# MaximConnections.net
KiCad netlist of a schematic drawn in Altium Designer
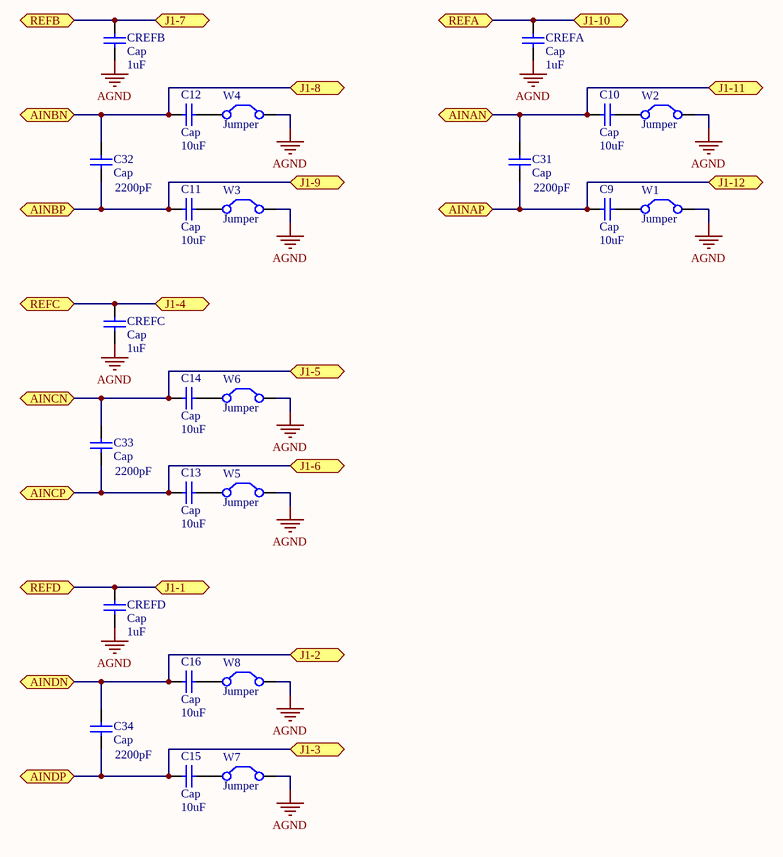
[diagram p0: MaximConnections.SchDoc]

(export (version "E")
  (design (tool "Eeschema 10.0.6"))
  (components
    (comp (ref "C9")
      (value "Cap")
      (footprint "RAD-0.3")
      (description "Capacitor")
      (fields (field (name "ALTIUM_VALUE") "10uF") (field (name "PUBLISHER") "Altium Limited"))
      (libsource (lib "Miscellaneous Devices") (part "Cap"))
    )
    (comp (ref "C10")
      (value "Cap")
      (footprint "RAD-0.3")
      (description "Capacitor")
      (fields (field (name "ALTIUM_VALUE") "10uF") (field (name "PUBLISHER") "Altium Limited"))
      (libsource (lib "Miscellaneous Devices") (part "Cap"))
    )
    (comp (ref "C11")
      (value "Cap")
      (footprint "RAD-0.3")
      (description "Capacitor")
      (fields (field (name "ALTIUM_VALUE") "10uF") (field (name "PUBLISHER") "Altium Limited"))
      (libsource (lib "Miscellaneous Devices") (part "Cap"))
    )
    (comp (ref "C12")
      (value "Cap")
      (footprint "RAD-0.3")
      (description "Capacitor")
      (fields (field (name "ALTIUM_VALUE") "10uF") (field (name "PUBLISHER") "Altium Limited"))
      (libsource (lib "Miscellaneous Devices") (part "Cap"))
    )
    (comp (ref "C13")
      (value "Cap")
      (footprint "RAD-0.3")
      (description "Capacitor")
      (fields (field (name "ALTIUM_VALUE") "10uF") (field (name "PUBLISHER") "Altium Limited"))
      (libsource (lib "Miscellaneous Devices") (part "Cap"))
    )
    (comp (ref "C14")
      (value "Cap")
      (footprint "RAD-0.3")
      (description "Capacitor")
      (fields (field (name "ALTIUM_VALUE") "10uF") (field (name "PUBLISHER") "Altium Limited"))
      (libsource (lib "Miscellaneous Devices") (part "Cap"))
    )
    (comp (ref "C15")
      (value "Cap")
      (footprint "RAD-0.3")
      (description "Capacitor")
      (fields (field (name "ALTIUM_VALUE") "10uF") (field (name "PUBLISHER") "Altium Limited"))
      (libsource (lib "Miscellaneous Devices") (part "Cap"))
    )
    (comp (ref "C16")
      (value "Cap")
      (footprint "RAD-0.3")
      (description "Capacitor")
      (fields (field (name "ALTIUM_VALUE") "10uF") (field (name "PUBLISHER") "Altium Limited"))
      (libsource (lib "Miscellaneous Devices") (part "Cap"))
    )
    (comp (ref "C31")
      (value "Cap")
      (footprint "RAD-0.3")
      (description "Capacitor")
      (fields (field (name "ALTIUM_VALUE") "2200pF") (field (name "PUBLISHER") "Altium Limited"))
      (libsource (lib "Miscellaneous Devices") (part "Cap"))
    )
    (comp (ref "C32")
      (value "Cap")
      (footprint "RAD-0.3")
      (description "Capacitor")
      (fields (field (name "ALTIUM_VALUE") "2200pF") (field (name "PUBLISHER") "Altium Limited"))
      (libsource (lib "Miscellaneous Devices") (part "Cap"))
    )
    (comp (ref "C33")
      (value "Cap")
      (footprint "RAD-0.3")
      (description "Capacitor")
      (fields (field (name "ALTIUM_VALUE") "2200pF") (field (name "PUBLISHER") "Altium Limited"))
      (libsource (lib "Miscellaneous Devices") (part "Cap"))
    )
    (comp (ref "C34")
      (value "Cap")
      (footprint "RAD-0.3")
      (description "Capacitor")
      (fields (field (name "ALTIUM_VALUE") "2200pF") (field (name "PUBLISHER") "Altium Limited"))
      (libsource (lib "Miscellaneous Devices") (part "Cap"))
    )
    (comp (ref "CREFA")
      (value "Cap")
      (footprint "RAD-0.3")
      (description "Capacitor")
      (fields (field (name "ALTIUM_VALUE") "1uF") (field (name "PUBLISHER") "Altium Limited"))
      (libsource (lib "Miscellaneous Devices") (part "Cap"))
    )
    (comp (ref "CREFB")
      (value "Cap")
      (footprint "RAD-0.3")
      (description "Capacitor")
      (fields (field (name "ALTIUM_VALUE") "1uF") (field (name "PUBLISHER") "Altium Limited"))
      (libsource (lib "Miscellaneous Devices") (part "Cap"))
    )
    (comp (ref "CREFC")
      (value "Cap")
      (footprint "RAD-0.3")
      (description "Capacitor")
      (fields (field (name "ALTIUM_VALUE") "1uF") (field (name "PUBLISHER") "Altium Limited"))
      (libsource (lib "Miscellaneous Devices") (part "Cap"))
    )
    (comp (ref "CREFD")
      (value "Cap")
      (footprint "RAD-0.3")
      (description "Capacitor")
      (fields (field (name "ALTIUM_VALUE") "1uF") (field (name "PUBLISHER") "Altium Limited"))
      (libsource (lib "Miscellaneous Devices") (part "Cap"))
    )
    (comp (ref "W1")
      (value "Jumper")
      (footprint "RAD-0.2")
      (description "Jumper Wire")
      (fields (field (name "PUBLISHER") "Altium Limited"))
      (libsource (lib "Miscellaneous Devices") (part "Jumper"))
    )
    (comp (ref "W2")
      (value "Jumper")
      (footprint "RAD-0.2")
      (description "Jumper Wire")
      (fields (field (name "PUBLISHER") "Altium Limited"))
      (libsource (lib "Miscellaneous Devices") (part "Jumper"))
    )
    (comp (ref "W3")
      (value "Jumper")
      (footprint "RAD-0.2")
      (description "Jumper Wire")
      (fields (field (name "PUBLISHER") "Altium Limited"))
      (libsource (lib "Miscellaneous Devices") (part "Jumper"))
    )
    (comp (ref "W4")
      (value "Jumper")
      (footprint "RAD-0.2")
      (description "Jumper Wire")
      (fields (field (name "PUBLISHER") "Altium Limited"))
      (libsource (lib "Miscellaneous Devices") (part "Jumper"))
    )
    (comp (ref "W5")
      (value "Jumper")
      (footprint "RAD-0.2")
      (description "Jumper Wire")
      (fields (field (name "PUBLISHER") "Altium Limited"))
      (libsource (lib "Miscellaneous Devices") (part "Jumper"))
    )
    (comp (ref "W6")
      (value "Jumper")
      (footprint "RAD-0.2")
      (description "Jumper Wire")
      (fields (field (name "PUBLISHER") "Altium Limited"))
      (libsource (lib "Miscellaneous Devices") (part "Jumper"))
    )
    (comp (ref "W7")
      (value "Jumper")
      (footprint "RAD-0.2")
      (description "Jumper Wire")
      (fields (field (name "PUBLISHER") "Altium Limited"))
      (libsource (lib "Miscellaneous Devices") (part "Jumper"))
    )
    (comp (ref "W8")
      (value "Jumper")
      (footprint "RAD-0.2")
      (description "Jumper Wire")
      (fields (field (name "PUBLISHER") "Altium Limited"))
      (libsource (lib "Miscellaneous Devices") (part "Jumper"))
    )
  )
  (nets
    (net (code "1") (name "/AINAN") (class "Default")
      (node (ref "C10") (pin "2") (pinfunction "2_2") (pintype "passive"))
      (node (ref "C31") (pin "2") (pinfunction "2_2") (pintype "passive"))
    )
    (net (code "2") (name "/AINAP") (class "Default")
      (node (ref "C31") (pin "1") (pinfunction "1_1") (pintype "passive"))
      (node (ref "C9") (pin "2") (pinfunction "2_2") (pintype "passive"))
    )
    (net (code "3") (name "/AINBN") (class "Default")
      (node (ref "C12") (pin "2") (pinfunction "2_2") (pintype "passive"))
      (node (ref "C32") (pin "2") (pinfunction "2_2") (pintype "passive"))
    )
    (net (code "4") (name "/AINBP") (class "Default")
      (node (ref "C11") (pin "2") (pinfunction "2_2") (pintype "passive"))
      (node (ref "C32") (pin "1") (pinfunction "1_1") (pintype "passive"))
    )
    (net (code "5") (name "/AINCN") (class "Default")
      (node (ref "C14") (pin "2") (pinfunction "2_2") (pintype "passive"))
      (node (ref "C33") (pin "2") (pinfunction "2_2") (pintype "passive"))
    )
    (net (code "6") (name "/AINCP") (class "Default")
      (node (ref "C13") (pin "2") (pinfunction "2_2") (pintype "passive"))
      (node (ref "C33") (pin "1") (pinfunction "1_1") (pintype "passive"))
    )
    (net (code "7") (name "/AINDN") (class "Default")
      (node (ref "C16") (pin "2") (pinfunction "2_2") (pintype "passive"))
      (node (ref "C34") (pin "2") (pinfunction "2_2") (pintype "passive"))
    )
    (net (code "8") (name "/AINDP") (class "Default")
      (node (ref "C15") (pin "2") (pinfunction "2_2") (pintype "passive"))
      (node (ref "C34") (pin "1") (pinfunction "1_1") (pintype "passive"))
    )
    (net (code "9") (name "/J1-1") (class "Default")
      (node (ref "CREFD") (pin "2") (pinfunction "2_2") (pintype "passive"))
    )
    (net (code "10") (name "/J1-4") (class "Default")
      (node (ref "CREFC") (pin "2") (pinfunction "2_2") (pintype "passive"))
    )
    (net (code "11") (name "/J1-7") (class "Default")
      (node (ref "CREFB") (pin "2") (pinfunction "2_2") (pintype "passive"))
    )
    (net (code "12") (name "/J1-10") (class "Default")
      (node (ref "CREFA") (pin "2") (pinfunction "2_2") (pintype "passive"))
    )
    (net (code "13") (name "AGND") (class "Default")
      (node (ref "CREFA") (pin "1") (pinfunction "1_1") (pintype "passive"))
      (node (ref "CREFB") (pin "1") (pinfunction "1_1") (pintype "passive"))
      (node (ref "CREFC") (pin "1") (pinfunction "1_1") (pintype "passive"))
      (node (ref "CREFD") (pin "1") (pinfunction "1_1") (pintype "passive"))
      (node (ref "W1") (pin "2") (pinfunction "C2_2") (pintype "passive"))
      (node (ref "W2") (pin "2") (pinfunction "C2_2") (pintype "passive"))
      (node (ref "W3") (pin "2") (pinfunction "C2_2") (pintype "passive"))
      (node (ref "W4") (pin "2") (pinfunction "C2_2") (pintype "passive"))
      (node (ref "W5") (pin "2") (pinfunction "C2_2") (pintype "passive"))
      (node (ref "W6") (pin "2") (pinfunction "C2_2") (pintype "passive"))
      (node (ref "W7") (pin "2") (pinfunction "C2_2") (pintype "passive"))
      (node (ref "W8") (pin "2") (pinfunction "C2_2") (pintype "passive"))
    )
    (net (code "14") (name "Net-(W1-C1)") (class "Default")
      (node (ref "C9") (pin "1") (pinfunction "1_1") (pintype "passive"))
      (node (ref "W1") (pin "1") (pinfunction "C1_1") (pintype "passive"))
    )
    (net (code "15") (name "Net-(W2-C1)") (class "Default")
      (node (ref "C10") (pin "1") (pinfunction "1_1") (pintype "passive"))
      (node (ref "W2") (pin "1") (pinfunction "C1_1") (pintype "passive"))
    )
    (net (code "16") (name "Net-(W3-C1)") (class "Default")
      (node (ref "C11") (pin "1") (pinfunction "1_1") (pintype "passive"))
      (node (ref "W3") (pin "1") (pinfunction "C1_1") (pintype "passive"))
    )
    (net (code "17") (name "Net-(W4-C1)") (class "Default")
      (node (ref "C12") (pin "1") (pinfunction "1_1") (pintype "passive"))
      (node (ref "W4") (pin "1") (pinfunction "C1_1") (pintype "passive"))
    )
    (net (code "18") (name "Net-(W5-C1)") (class "Default")
      (node (ref "C13") (pin "1") (pinfunction "1_1") (pintype "passive"))
      (node (ref "W5") (pin "1") (pinfunction "C1_1") (pintype "passive"))
    )
    (net (code "19") (name "Net-(W6-C1)") (class "Default")
      (node (ref "C14") (pin "1") (pinfunction "1_1") (pintype "passive"))
      (node (ref "W6") (pin "1") (pinfunction "C1_1") (pintype "passive"))
    )
    (net (code "20") (name "Net-(W7-C1)") (class "Default")
      (node (ref "C15") (pin "1") (pinfunction "1_1") (pintype "passive"))
      (node (ref "W7") (pin "1") (pinfunction "C1_1") (pintype "passive"))
    )
    (net (code "21") (name "Net-(W8-C1)") (class "Default")
      (node (ref "C16") (pin "1") (pinfunction "1_1") (pintype "passive"))
      (node (ref "W8") (pin "1") (pinfunction "C1_1") (pintype "passive"))
    )
  )
)
